# Shematics.net
KiCad netlist of a schematic drawn in Altium Designer
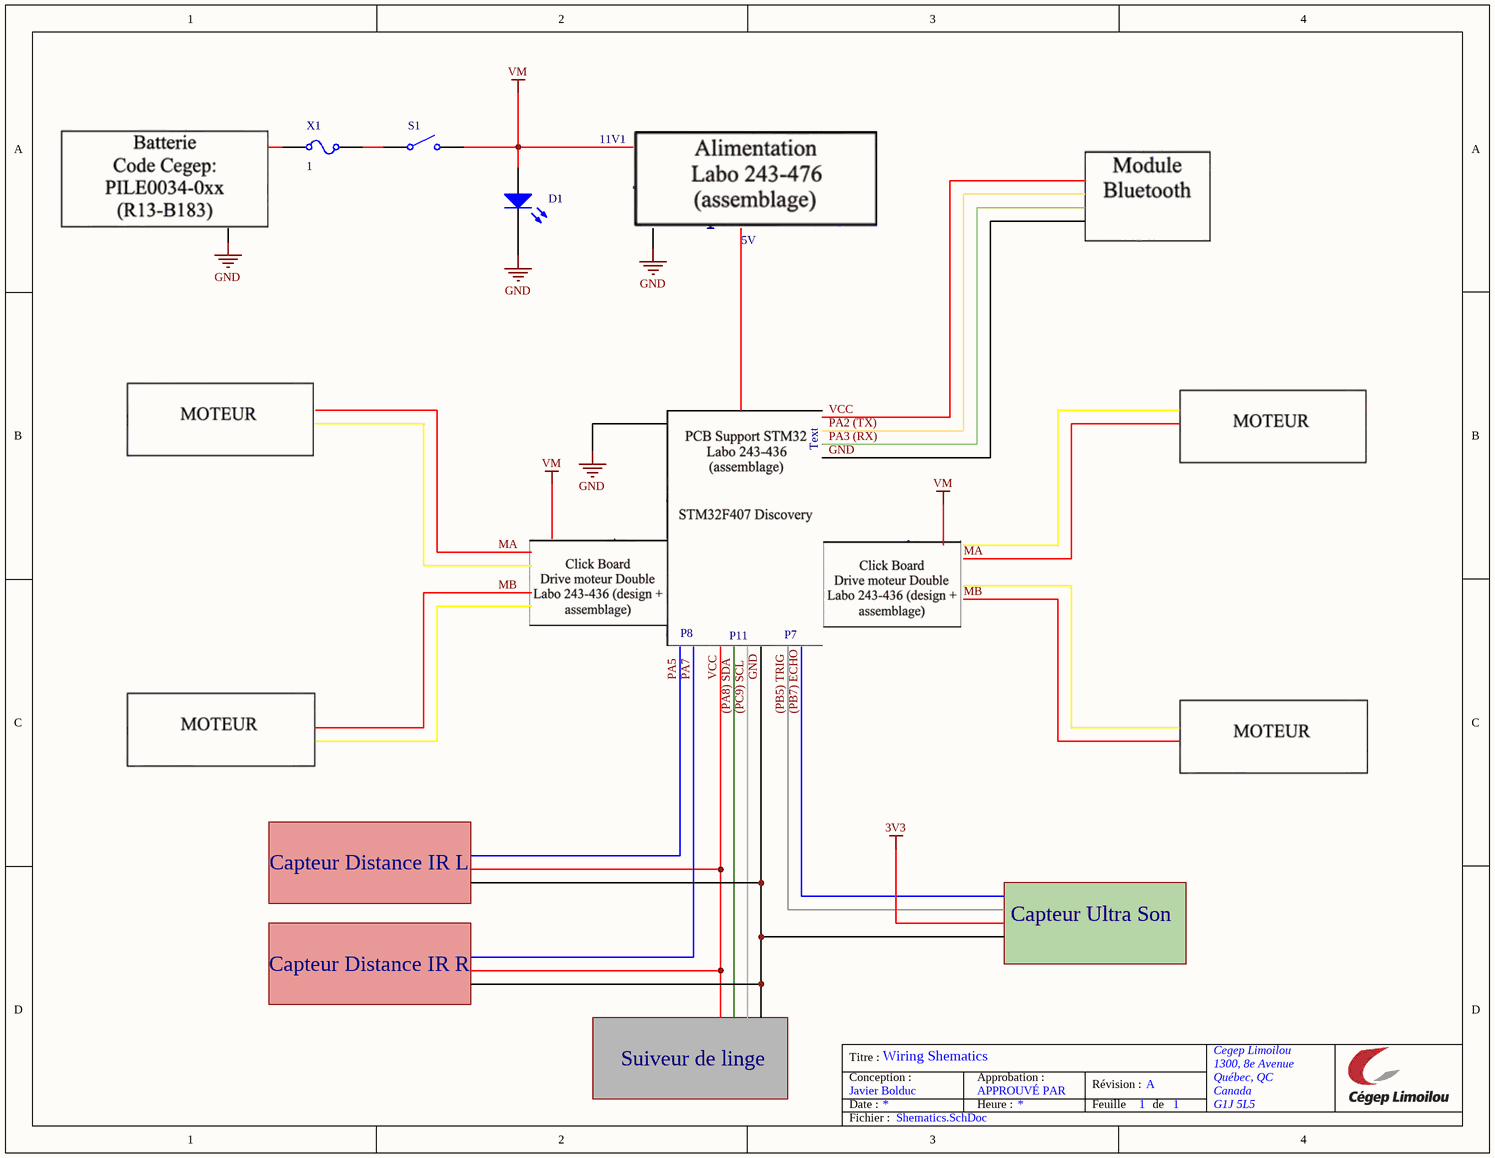
[diagram p0: Shematics.SchDoc]

(export (version "E")
  (design (tool "Eeschema 10.0.6"))
  (components
    (comp (ref "D1")
      (value "Light-Emitting Diode")
      (libsource (lib "Simulation Generic Components") (part "LED"))
    )
    (comp (ref "S1")
      (value "Single-Pole, Single-Throw Switch")
      (libsource (lib "Simulation Generic Components") (part "SPST SW"))
    )
    (comp (ref "X1")
      (value "Fuse")
      (fields (field (name "CURRENT") "1"))
      (libsource (lib "Simulation Generic Components") (part "Fuse"))
    )
  )
  (nets
    (net (code "13") (name "GND") (class "Default")
      (node (ref "D1") (pin "2") (pinfunction "K_2") (pintype "passive"))
    )
    (net (code "14") (name "Net-(S1-Pad1)") (class "Default")
      (node (ref "S1") (pin "1") (pinfunction "1_1") (pintype "passive"))
      (node (ref "X1") (pin "2") (pinfunction "2_2") (pintype "passive"))
    )
    (net (code "15") (name "VM") (class "Default")
      (node (ref "D1") (pin "1") (pinfunction "A_1") (pintype "passive"))
      (node (ref "S1") (pin "2") (pinfunction "2_2") (pintype "passive"))
    )
    (net (code "16") (name "unconnected-(X1-Pad1)") (class "Default")
      (node (ref "X1") (pin "1") (pinfunction "1_1") (pintype "passive"))
    )
  )
)
